# 1_InputPowerProtection.net
KiCad netlist of a schematic drawn in Altium Designer
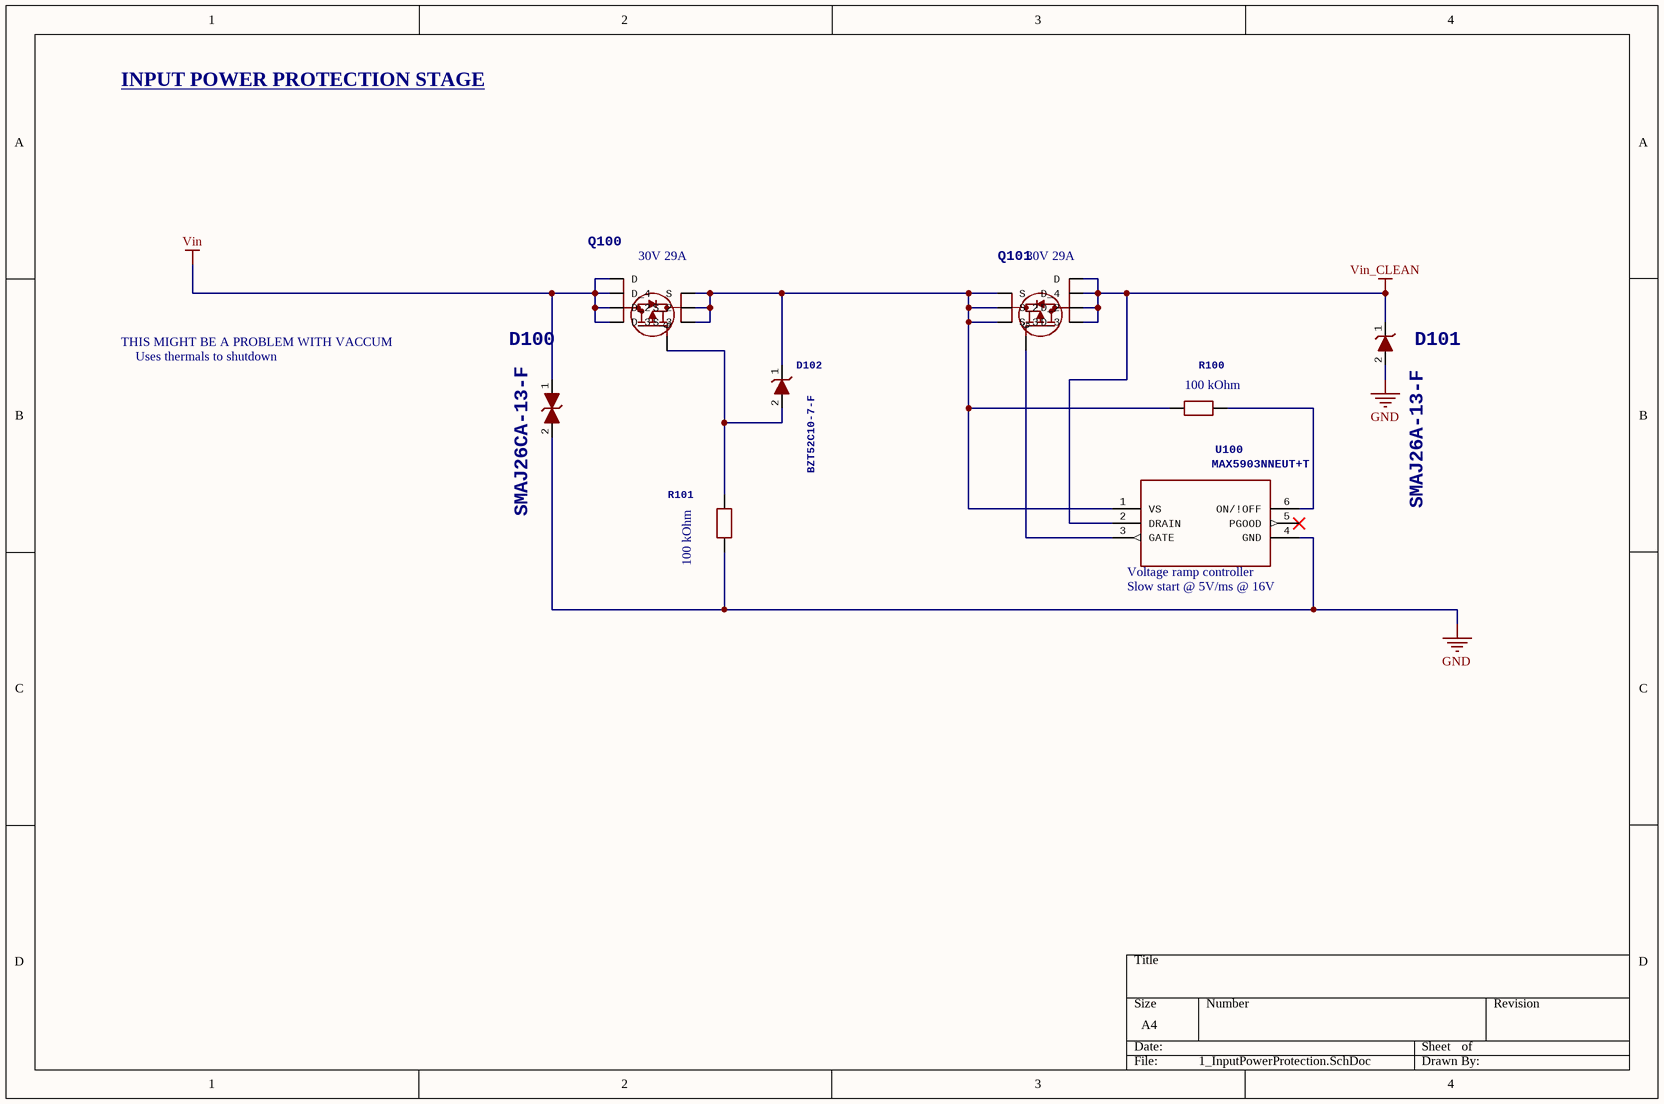
[diagram p0: 1_InputPowerProtection.SchDoc]

(export (version "E")
  (design (tool "Eeschema 10.0.6"))
  (components
    (comp (ref "D100")
      (value "SMAJ26CA-13-F")
      (footprint "DIODE_DO-214AC")
      (description "Diode TVS Bidirectional 26V")
      (fields (field (name "MANUFACTURER_PART_NUMBER") "SMAJ26A-13-F"))
      (libsource (lib "Passives") (part "SMAJ26CA-13-F"))
    )
    (comp (ref "D101")
      (value "SMAJ26A-13-F")
      (footprint "DIODE_DO-214AC")
      (description "Diode TVS 26V")
      (fields (field (name "COPYRIGHT") "Copyright (C) 2022 Ultra Librarian. All rights reserved."))
      (libsource (lib "Passives") (part "SMAJ26A-13-F"))
    )
    (comp (ref "D102")
      (value "BZT52C10-7-F")
      (footprint "DIODE_SOD-123")
      (description "Diode Zener 10V 370mW")
      (fields (field (name "MOUSER_PART_NUMBER") "621-BZT52C10-F"))
      (libsource (lib "Passives") (part "BZT52C10-7-F"))
    )
    (comp (ref "Q100")
      (value "30V 29A")
      (footprint "MOSFET_SOIC-8")
      (description "P-Channel 30V 29A 5mOHm")
      (fields
        (field (name "MANUFACTURER_PART_NUMBER") "SI4459ADY-T1-GE3")
        (field (name "Comment") "SI4459ADY")
      )
      (libsource (lib "FETs") (part "SI4459ADY-T1-GE3SO_ADY-T1-GE3_VIS-M"))
    )
    (comp (ref "Q101")
      (value "30V 29A")
      (footprint "MOSFET_SOIC-8")
      (description "P-Channel 30V 29A 5mOHm")
      (fields
        (field (name "MANUFACTURER_PART_NUMBER") "SI4459ADY-T1-GE3")
        (field (name "Comment") "SI4459ADY")
      )
      (libsource (lib "FETs") (part "SI4459ADY-T1-GE3SO_ADY-T1-GE3_VIS-M"))
    )
    (comp (ref "R100")
      (value "100 kOhm")
      (footprint "RES_0603")
      (description "Res 100kOhm 1/10W 0603")
      (fields (field (name "PARTNUMBER") "ERJ3GEYJ104V"))
      (libsource (lib "Passives") (part "ERJ3GEYJ104V"))
    )
    (comp (ref "R101")
      (value "100 kOhm")
      (footprint "RES_0603")
      (description "Res 100kOhm 1/10W 0603")
      (fields (field (name "PARTNUMBER") "ERJ3GEYJ104V"))
      (libsource (lib "Passives") (part "ERJ3GEYJ104V"))
    )
    (comp (ref "U100")
      (value "MAX5903NNEUT+T")
      (footprint "HOTSWAP_SOT-6")
      (description "Hot Swap Controller MAX5903NNEUT+T")
      (fields
        (field (name "MANUFACTURER") "Analog Devices Inc")
        (field (name "COPYRIGHT") "Copyright (C) 2023 Ultra Librarian. All rights reserved.")
      )
      (libsource (lib "FETs") (part "MAX5903NNEUT+T"))
    )
  )
  (nets
    (net (code "1") (name "GND") (class "Default")
      (node (ref "D100") (pin "2") (pinfunction "2_2") (pintype "passive"))
      (node (ref "D101") (pin "2") (pinfunction "2_2") (pintype "passive"))
      (node (ref "R101") (pin "1") (pinfunction "1_1") (pintype "passive"))
      (node (ref "U100") (pin "4") (pinfunction "GND_4") (pintype "power_in"))
    )
    (net (code "2") (name "Net-(Q100-G)") (class "Default")
      (node (ref "D102") (pin "2") (pinfunction "2_2") (pintype "passive"))
      (node (ref "Q100") (pin "4") (pinfunction "G_4") (pintype "passive"))
      (node (ref "R101") (pin "2") (pinfunction "2_2") (pintype "passive"))
    )
    (net (code "3") (name "Net-(Q100-S)") (class "Default")
      (node (ref "D102") (pin "1") (pinfunction "1_1") (pintype "passive"))
      (node (ref "Q100") (pin "1") (pinfunction "S_3_1") (pintype "passive"))
      (node (ref "Q100") (pin "2") (pinfunction "S_2_2") (pintype "passive"))
      (node (ref "Q100") (pin "3") (pinfunction "S_3") (pintype "passive"))
      (node (ref "Q101") (pin "1") (pinfunction "S_3_1") (pintype "passive"))
      (node (ref "Q101") (pin "2") (pinfunction "S_2_2") (pintype "passive"))
      (node (ref "Q101") (pin "3") (pinfunction "S_3") (pintype "passive"))
      (node (ref "R100") (pin "1") (pinfunction "1_1") (pintype "passive"))
      (node (ref "U100") (pin "1") (pinfunction "VS_1") (pintype "power_in"))
    )
    (net (code "4") (name "Net-(Q101-G)") (class "Default")
      (node (ref "Q101") (pin "4") (pinfunction "G_4") (pintype "passive"))
      (node (ref "U100") (pin "3") (pinfunction "GATE_3") (pintype "output"))
    )
    (net (code "5") (name "Net-(U100-ON{slash}!OFF)") (class "Default")
      (node (ref "R100") (pin "2") (pinfunction "2_2") (pintype "passive"))
      (node (ref "U100") (pin "6") (pinfunction "ON/!OFF_6") (pintype "passive"))
    )
    (net (code "6") (name "Vin") (class "Default")
      (node (ref "D100") (pin "1") (pinfunction "1_1") (pintype "passive"))
      (node (ref "Q100") (pin "5") (pinfunction "D_3_5") (pintype "passive"))
      (node (ref "Q100") (pin "6") (pinfunction "D_2_6") (pintype "passive"))
      (node (ref "Q100") (pin "7") (pinfunction "D_4_7") (pintype "passive"))
      (node (ref "Q100") (pin "8") (pinfunction "D_8") (pintype "passive"))
    )
    (net (code "7") (name "Vin_CLEAN") (class "Default")
      (node (ref "D101") (pin "1") (pinfunction "1_1") (pintype "passive"))
      (node (ref "Q101") (pin "5") (pinfunction "D_3_5") (pintype "passive"))
      (node (ref "Q101") (pin "6") (pinfunction "D_2_6") (pintype "passive"))
      (node (ref "Q101") (pin "7") (pinfunction "D_4_7") (pintype "passive"))
      (node (ref "Q101") (pin "8") (pinfunction "D_8") (pintype "passive"))
      (node (ref "U100") (pin "2") (pinfunction "DRAIN_2") (pintype "passive"))
    )
    (net (code "8") (name "unconnected-(U100-PGOOD-Pad5)") (class "Default")
      (node (ref "U100") (pin "5") (pinfunction "PGOOD_5") (pintype "output+no_connect"))
    )
  )
)
